# 393det.net
KiCad netlist of a schematic drawn in EAGLE
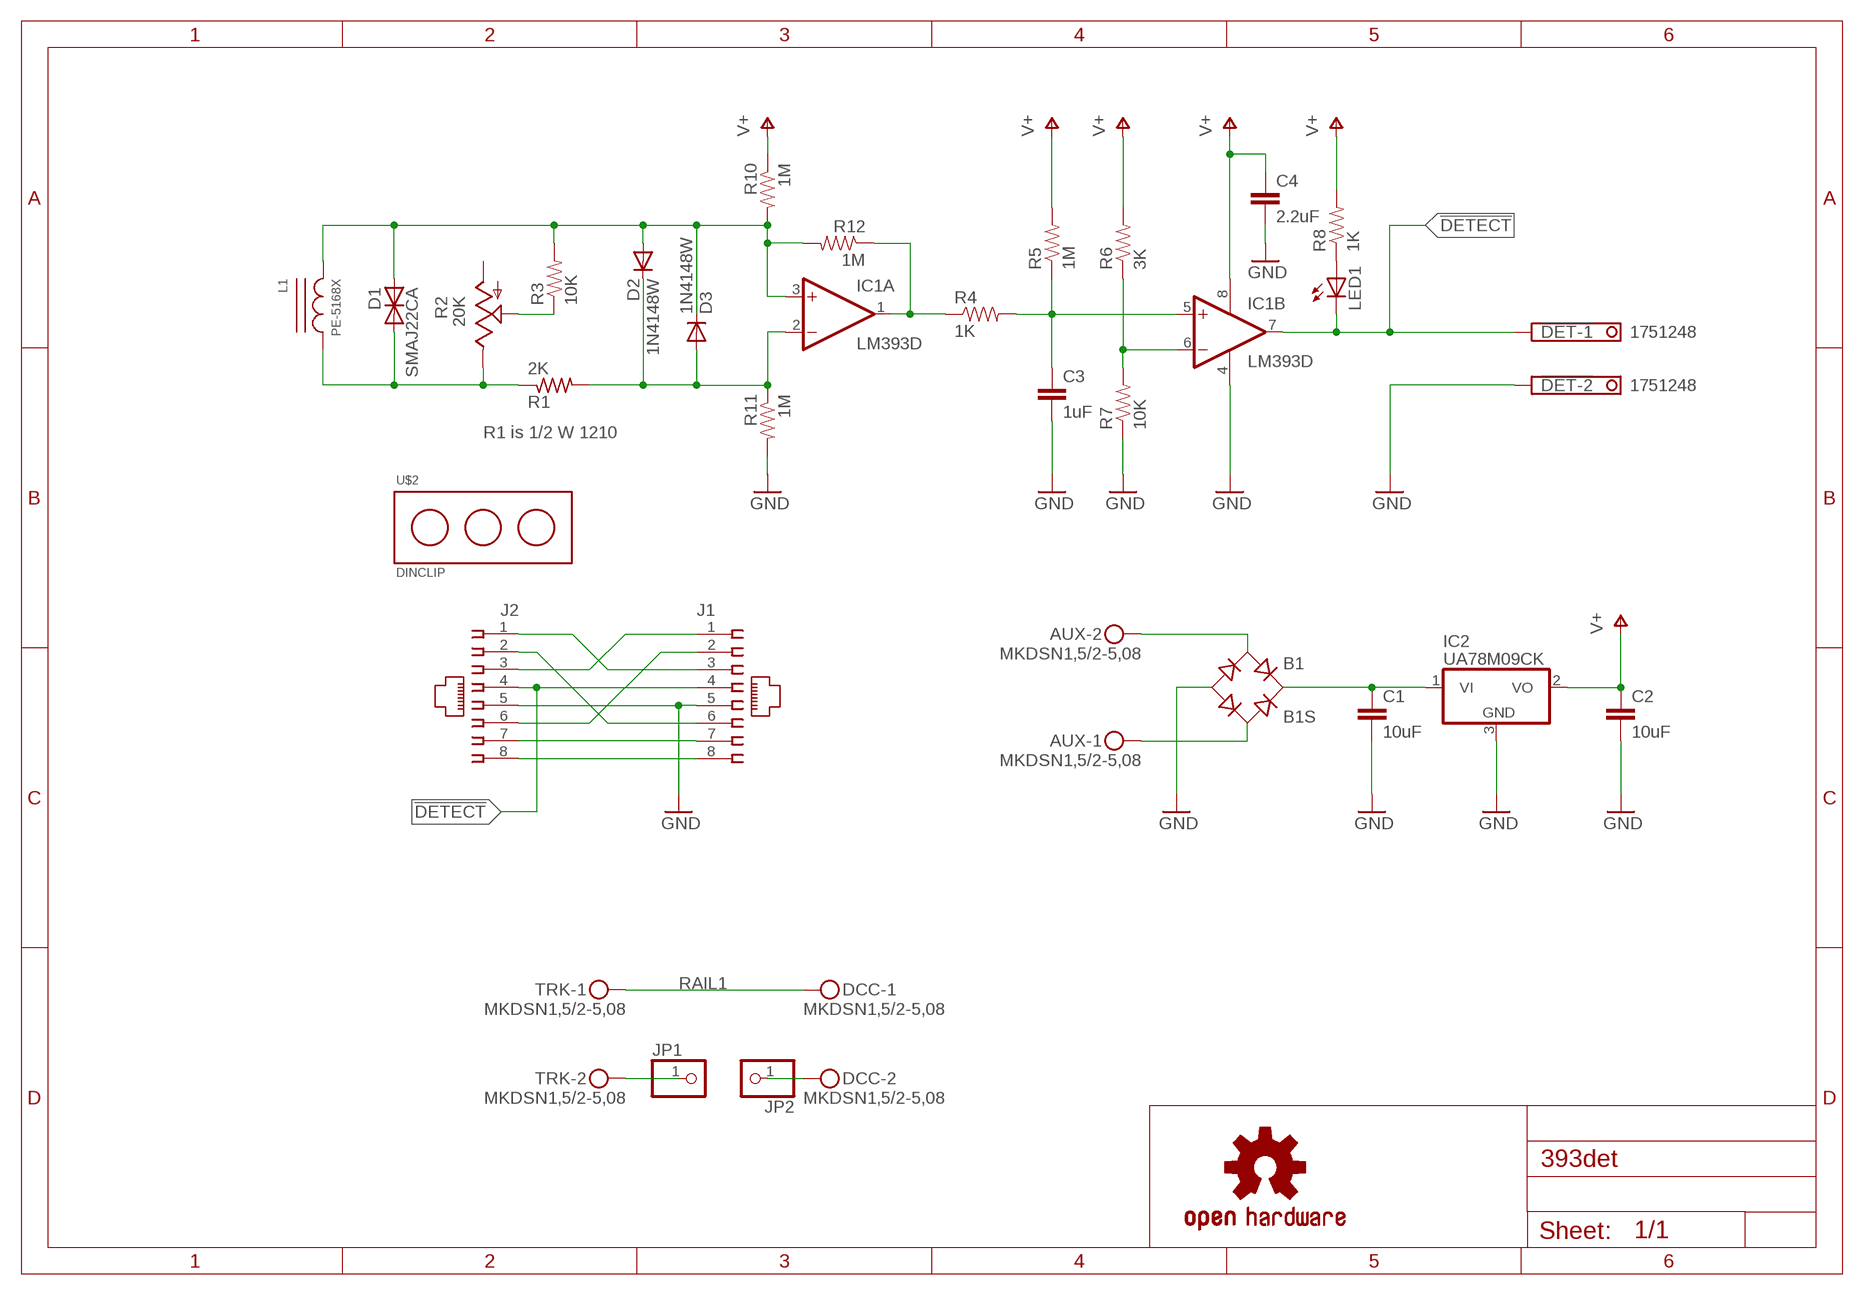
[diagram p0: schematic, sheet 1]

(export (version "E")
  (design (tool "Eeschema 10.0.6"))
  (components
    (comp (ref "!DET")
      (value "1751248")
      (footprint "eagle-import:1751248")
      (libsource (lib "eagle-import") (part "1751248"))
    )
    (comp (ref "AUX")
      (value "MKDSN1,5/2-5,08")
      (footprint "eagle-import:MKDSN1,5_2-5,08")
      (fields (field (name "MPN") "MKDSN 1,5/2-5.08"))
      (libsource (lib "eagle-import") (part "MKDSN1,5/2-5,08"))
    )
    (comp (ref "B1")
      (value "B1S")
      (footprint "eagle-import:MBS")
      (libsource (lib "eagle-import") (part "BS1"))
    )
    (comp (ref "C1")
      (value "10uF")
      (footprint "eagle-import:1210")
      (libsource (lib "eagle-import") (part "22UF-16V-20%-(1210)"))
    )
    (comp (ref "C2")
      (value "10uF")
      (footprint "eagle-import:1210")
      (libsource (lib "eagle-import") (part "22UF-16V-20%-(1210)"))
    )
    (comp (ref "C3")
      (value "1uF")
      (footprint "eagle-import:0805")
      (libsource (lib "eagle-import") (part "CAP0805"))
    )
    (comp (ref "C4")
      (value "2.2uF")
      (footprint "eagle-import:0805")
      (libsource (lib "eagle-import") (part "CAP0805"))
    )
    (comp (ref "D1")
      (value "SMAJ22CA")
      (footprint "eagle-import:SMA")
      (libsource (lib "eagle-import") (part "SMAJ22CA{dblquote}"))
    )
    (comp (ref "D2")
      (value "1N4148W")
      (footprint "eagle-import:SOD123")
      (libsource (lib "eagle-import") (part "DIODE-SOD123"))
    )
    (comp (ref "D3")
      (value "1N4148W")
      (footprint "eagle-import:SOD123")
      (libsource (lib "eagle-import") (part "DIODE-SOD123"))
    )
    (comp (ref "DCC")
      (value "MKDSN1,5/2-5,08")
      (footprint "eagle-import:MKDSN1,5_2-5,08")
      (fields (field (name "MPN") "MKDSN 1,5/2-5.08"))
      (libsource (lib "eagle-import") (part "MKDSN1,5/2-5,08"))
    )
    (comp (ref "IC1")
      (value "LM393D")
      (footprint "eagle-import:SO08")
      (libsource (lib "eagle-import") (part "LM393D"))
    )
    (comp (ref "IC2")
      (value "UA78M09CK")
      (footprint "eagle-import:TO252")
      (libsource (lib "eagle-import") (part "78DT08"))
    )
    (comp (ref "J1")
      (value "215877-7")
      (footprint "eagle-import:215877-7")
      (libsource (lib "eagle-import") (part "215877-7"))
    )
    (comp (ref "J2")
      (value "215877-7")
      (footprint "eagle-import:215877-7")
      (libsource (lib "eagle-import") (part "215877-7"))
    )
    (comp (ref "JP1")
      (value "PINHD-1X1")
      (footprint "eagle-import:1X01")
      (libsource (lib "eagle-import") (part "PINHD-1X1"))
    )
    (comp (ref "JP2")
      (value "PINHD-1X1")
      (footprint "eagle-import:1X01")
      (libsource (lib "eagle-import") (part "PINHD-1X1"))
    )
    (comp (ref "L1")
      (value "PE-5168X")
      (footprint "eagle-import:PE-5168X")
      (libsource (lib "eagle-import") (part "PE-5168X"))
    )
    (comp (ref "LED1")
      (value "LED5MM")
      (footprint "eagle-import:LED5MM")
      (libsource (lib "eagle-import") (part "LED5MM"))
    )
    (comp (ref "R1")
      (value "2K")
      (footprint "eagle-import:R1206")
      (libsource (lib "eagle-import") (part "R-US_R1206"))
    )
    (comp (ref "R2")
      (value "20K")
      (footprint "eagle-import:B25U")
      (libsource (lib "eagle-import") (part "TRIM_US-B25U"))
    )
    (comp (ref "R3")
      (value "10K")
      (footprint "eagle-import:0805")
      (libsource (lib "eagle-import") (part "RESISTOR0805-RES"))
    )
    (comp (ref "R4")
      (value "1K")
      (footprint "eagle-import:0805")
      (libsource (lib "eagle-import") (part "RESISTOR0805-RES"))
    )
    (comp (ref "R5")
      (value "1M")
      (footprint "eagle-import:0805")
      (libsource (lib "eagle-import") (part "RESISTOR0805-RES"))
    )
    (comp (ref "R6")
      (value "3K")
      (footprint "eagle-import:0805")
      (libsource (lib "eagle-import") (part "RESISTOR0805-RES"))
    )
    (comp (ref "R7")
      (value "10K")
      (footprint "eagle-import:0805")
      (libsource (lib "eagle-import") (part "RESISTOR0805-RES"))
    )
    (comp (ref "R8")
      (value "1K")
      (footprint "eagle-import:0805")
      (libsource (lib "eagle-import") (part "RESISTOR0805-RES"))
    )
    (comp (ref "R10")
      (value "1M")
      (footprint "eagle-import:0805")
      (libsource (lib "eagle-import") (part "RESISTOR0805-RES"))
    )
    (comp (ref "R11")
      (value "1M")
      (footprint "eagle-import:0805")
      (libsource (lib "eagle-import") (part "RESISTOR0805-RES"))
    )
    (comp (ref "R12")
      (value "1M")
      (footprint "eagle-import:0805")
      (libsource (lib "eagle-import") (part "RESISTOR0805-RES"))
    )
    (comp (ref "TRK")
      (value "MKDSN1,5/2-5,08")
      (footprint "eagle-import:MKDSN1,5_2-5,08")
      (fields (field (name "MPN") "MKDSN 1,5/2-5.08"))
      (libsource (lib "eagle-import") (part "MKDSN1,5/2-5,08"))
    )
    (comp (ref "U$1")
      (value "OSHW-LOGOM")
      (footprint "eagle-import:OSHW-LOGO-M")
      (libsource (lib "eagle-import") (part "OSHW-LOGOM"))
    )
    (comp (ref "U$2")
      (value "DINCLIP")
      (footprint "eagle-import:1201578")
      (libsource (lib "eagle-import") (part "DINCLIP"))
    )
  )
  (nets
    (net (code "1") (name "/RAIL1") (class "Default")
      (node (ref "DCC") (pin "1") (pinfunction "KL_1") (pintype "passive"))
      (node (ref "TRK") (pin "1") (pinfunction "KL_1") (pintype "passive"))
    )
    (net (code "2") (name "/~{DETECT}") (class "Default")
      (node (ref "!DET") (pin "1") (pinfunction "K_1") (pintype "passive"))
      (node (ref "IC1") (pin "7") (pinfunction "OUT_7") (pintype "output"))
      (node (ref "J1") (pin "4") (pinfunction "4_4") (pintype "passive"))
      (node (ref "J2") (pin "4") (pinfunction "4_4") (pintype "passive"))
      (node (ref "LED1") (pin "K") (pinfunction "C_K") (pintype "passive"))
    )
    (net (code "3") (name "GND") (class "Default")
      (node (ref "!DET") (pin "2") (pinfunction "K_2") (pintype "passive"))
      (node (ref "B1") (pin "-") (pinfunction "-_-") (pintype "passive"))
      (node (ref "C1") (pin "2") (pinfunction "2_2") (pintype "passive"))
      (node (ref "C2") (pin "2") (pinfunction "2_2") (pintype "passive"))
      (node (ref "C3") (pin "2") (pinfunction "2_2") (pintype "passive"))
      (node (ref "C4") (pin "2") (pinfunction "2_2") (pintype "passive"))
      (node (ref "IC1") (pin "4") (pinfunction "V-_4") (pintype "power_in"))
      (node (ref "IC2") (pin "3") (pinfunction "GND_3") (pintype "passive"))
      (node (ref "J1") (pin "5") (pinfunction "5_5") (pintype "passive"))
      (node (ref "J2") (pin "5") (pinfunction "5_5") (pintype "passive"))
      (node (ref "R11") (pin "2") (pinfunction "2_2") (pintype "passive"))
      (node (ref "R7") (pin "1") (pinfunction "1_1") (pintype "passive"))
    )
    (net (code "4") (name "Net-(AUXA-KL)") (class "Default")
      (node (ref "AUX") (pin "1") (pinfunction "KL_1") (pintype "passive"))
      (node (ref "B1") (pin "AC2") (pinfunction "AC2_AC2") (pintype "passive"))
    )
    (net (code "5") (name "Net-(AUXB-KL)") (class "Default")
      (node (ref "AUX") (pin "2") (pinfunction "KL_2") (pintype "passive"))
      (node (ref "B1") (pin "AC1") (pinfunction "AC1_AC1") (pintype "passive"))
    )
    (net (code "6") (name "Net-(D1-1)") (class "Default")
      (node (ref "D1") (pin "A") (pinfunction "1_A") (pintype "passive"))
      (node (ref "D2") (pin "A") (pinfunction "A_A") (pintype "passive"))
      (node (ref "D3") (pin "C") (pinfunction "C_C") (pintype "passive"))
      (node (ref "IC1") (pin "3") (pinfunction "+IN_3") (pintype "input"))
      (node (ref "L1") (pin "P$2") (pinfunction "P$2_P$2") (pintype "bidirectional"))
      (node (ref "R10") (pin "2") (pinfunction "2_2") (pintype "passive"))
      (node (ref "R12") (pin "2") (pinfunction "2_2") (pintype "passive"))
      (node (ref "R3") (pin "2") (pinfunction "2_2") (pintype "passive"))
    )
    (net (code "7") (name "Net-(D1-2)") (class "Default")
      (node (ref "D1") (pin "C") (pinfunction "2_C") (pintype "passive"))
      (node (ref "L1") (pin "P$1") (pinfunction "P$1_P$1") (pintype "bidirectional"))
      (node (ref "R1") (pin "1") (pinfunction "1_1") (pintype "passive"))
      (node (ref "R2") (pin "E") (pinfunction "E_E") (pintype "passive"))
    )
    (net (code "8") (name "Net-(DCCB-KL)") (class "Default")
      (node (ref "DCC") (pin "2") (pinfunction "KL_2") (pintype "passive"))
      (node (ref "JP2") (pin "1") (pinfunction "1_1") (pintype "passive"))
    )
    (net (code "9") (name "Net-(IC1A--IN)") (class "Default")
      (node (ref "D2") (pin "C") (pinfunction "C_C") (pintype "passive"))
      (node (ref "D3") (pin "A") (pinfunction "A_A") (pintype "passive"))
      (node (ref "IC1") (pin "2") (pinfunction "-IN_2") (pintype "input"))
      (node (ref "R1") (pin "2") (pinfunction "2_2") (pintype "passive"))
      (node (ref "R11") (pin "1") (pinfunction "1_1") (pintype "passive"))
    )
    (net (code "10") (name "Net-(IC1A-OUT)") (class "Default")
      (node (ref "IC1") (pin "1") (pinfunction "OUT_1") (pintype "output"))
      (node (ref "R12") (pin "1") (pinfunction "1_1") (pintype "passive"))
      (node (ref "R4") (pin "1") (pinfunction "1_1") (pintype "passive"))
    )
    (net (code "11") (name "Net-(IC1B-+IN)") (class "Default")
      (node (ref "C3") (pin "1") (pinfunction "1_1") (pintype "passive"))
      (node (ref "IC1") (pin "5") (pinfunction "+IN_5") (pintype "input"))
      (node (ref "R4") (pin "2") (pinfunction "2_2") (pintype "passive"))
      (node (ref "R5") (pin "1") (pinfunction "1_1") (pintype "passive"))
    )
    (net (code "12") (name "Net-(IC1B--IN)") (class "Default")
      (node (ref "IC1") (pin "6") (pinfunction "-IN_6") (pintype "input"))
      (node (ref "R6") (pin "1") (pinfunction "1_1") (pintype "passive"))
      (node (ref "R7") (pin "2") (pinfunction "2_2") (pintype "passive"))
    )
    (net (code "13") (name "Net-(IC2-VI)") (class "Default")
      (node (ref "B1") (pin "+") (pinfunction "+_+") (pintype "passive"))
      (node (ref "C1") (pin "1") (pinfunction "1_1") (pintype "passive"))
      (node (ref "IC2") (pin "1") (pinfunction "VI_1") (pintype "input"))
    )
    (net (code "14") (name "Net-(J1-Pad1)") (class "Default")
      (node (ref "J1") (pin "1") (pinfunction "1_1") (pintype "passive"))
      (node (ref "J2") (pin "3") (pinfunction "3_3") (pintype "passive"))
    )
    (net (code "15") (name "Net-(J1-Pad2)") (class "Default")
      (node (ref "J1") (pin "2") (pinfunction "2_2") (pintype "passive"))
      (node (ref "J2") (pin "6") (pinfunction "6_6") (pintype "passive"))
    )
    (net (code "16") (name "Net-(J1-Pad3)") (class "Default")
      (node (ref "J1") (pin "3") (pinfunction "3_3") (pintype "passive"))
      (node (ref "J2") (pin "1") (pinfunction "1_1") (pintype "passive"))
    )
    (net (code "17") (name "Net-(J1-Pad6)") (class "Default")
      (node (ref "J1") (pin "6") (pinfunction "6_6") (pintype "passive"))
      (node (ref "J2") (pin "2") (pinfunction "2_2") (pintype "passive"))
    )
    (net (code "18") (name "Net-(J1-Pad7)") (class "Default")
      (node (ref "J1") (pin "7") (pinfunction "7_7") (pintype "passive"))
      (node (ref "J2") (pin "7") (pinfunction "7_7") (pintype "passive"))
    )
    (net (code "19") (name "Net-(J1-Pad8)") (class "Default")
      (node (ref "J1") (pin "8") (pinfunction "8_8") (pintype "passive"))
      (node (ref "J2") (pin "8") (pinfunction "8_8") (pintype "passive"))
    )
    (net (code "20") (name "Net-(LED1-PadA)") (class "Default")
      (node (ref "LED1") (pin "A") (pinfunction "A_A") (pintype "passive"))
      (node (ref "R8") (pin "1") (pinfunction "1_1") (pintype "passive"))
    )
    (net (code "21") (name "Net-(R2-PadS)") (class "Default")
      (node (ref "R2") (pin "S") (pinfunction "S_S") (pintype "passive"))
      (node (ref "R3") (pin "1") (pinfunction "1_1") (pintype "passive"))
    )
    (net (code "22") (name "Net-(TRKB-KL)") (class "Default")
      (node (ref "JP1") (pin "1") (pinfunction "1_1") (pintype "passive"))
      (node (ref "TRK") (pin "2") (pinfunction "KL_2") (pintype "passive"))
    )
    (net (code "23") (name "V+") (class "Default")
      (node (ref "C2") (pin "1") (pinfunction "1_1") (pintype "passive"))
      (node (ref "C4") (pin "1") (pinfunction "1_1") (pintype "passive"))
      (node (ref "IC1") (pin "8") (pinfunction "V+_8") (pintype "power_in"))
      (node (ref "IC2") (pin "2") (pinfunction "VO_2") (pintype "passive"))
      (node (ref "R10") (pin "1") (pinfunction "1_1") (pintype "passive"))
      (node (ref "R5") (pin "2") (pinfunction "2_2") (pintype "passive"))
      (node (ref "R6") (pin "2") (pinfunction "2_2") (pintype "passive"))
      (node (ref "R8") (pin "2") (pinfunction "2_2") (pintype "passive"))
    )
    (net (code "24") (name "unconnected-(R2-PadA)") (class "Default")
      (node (ref "R2") (pin "A") (pinfunction "A_A") (pintype "passive"))
    )
  )
)
